# main.net
KiCad netlist of a schematic drawn in Altium Designer
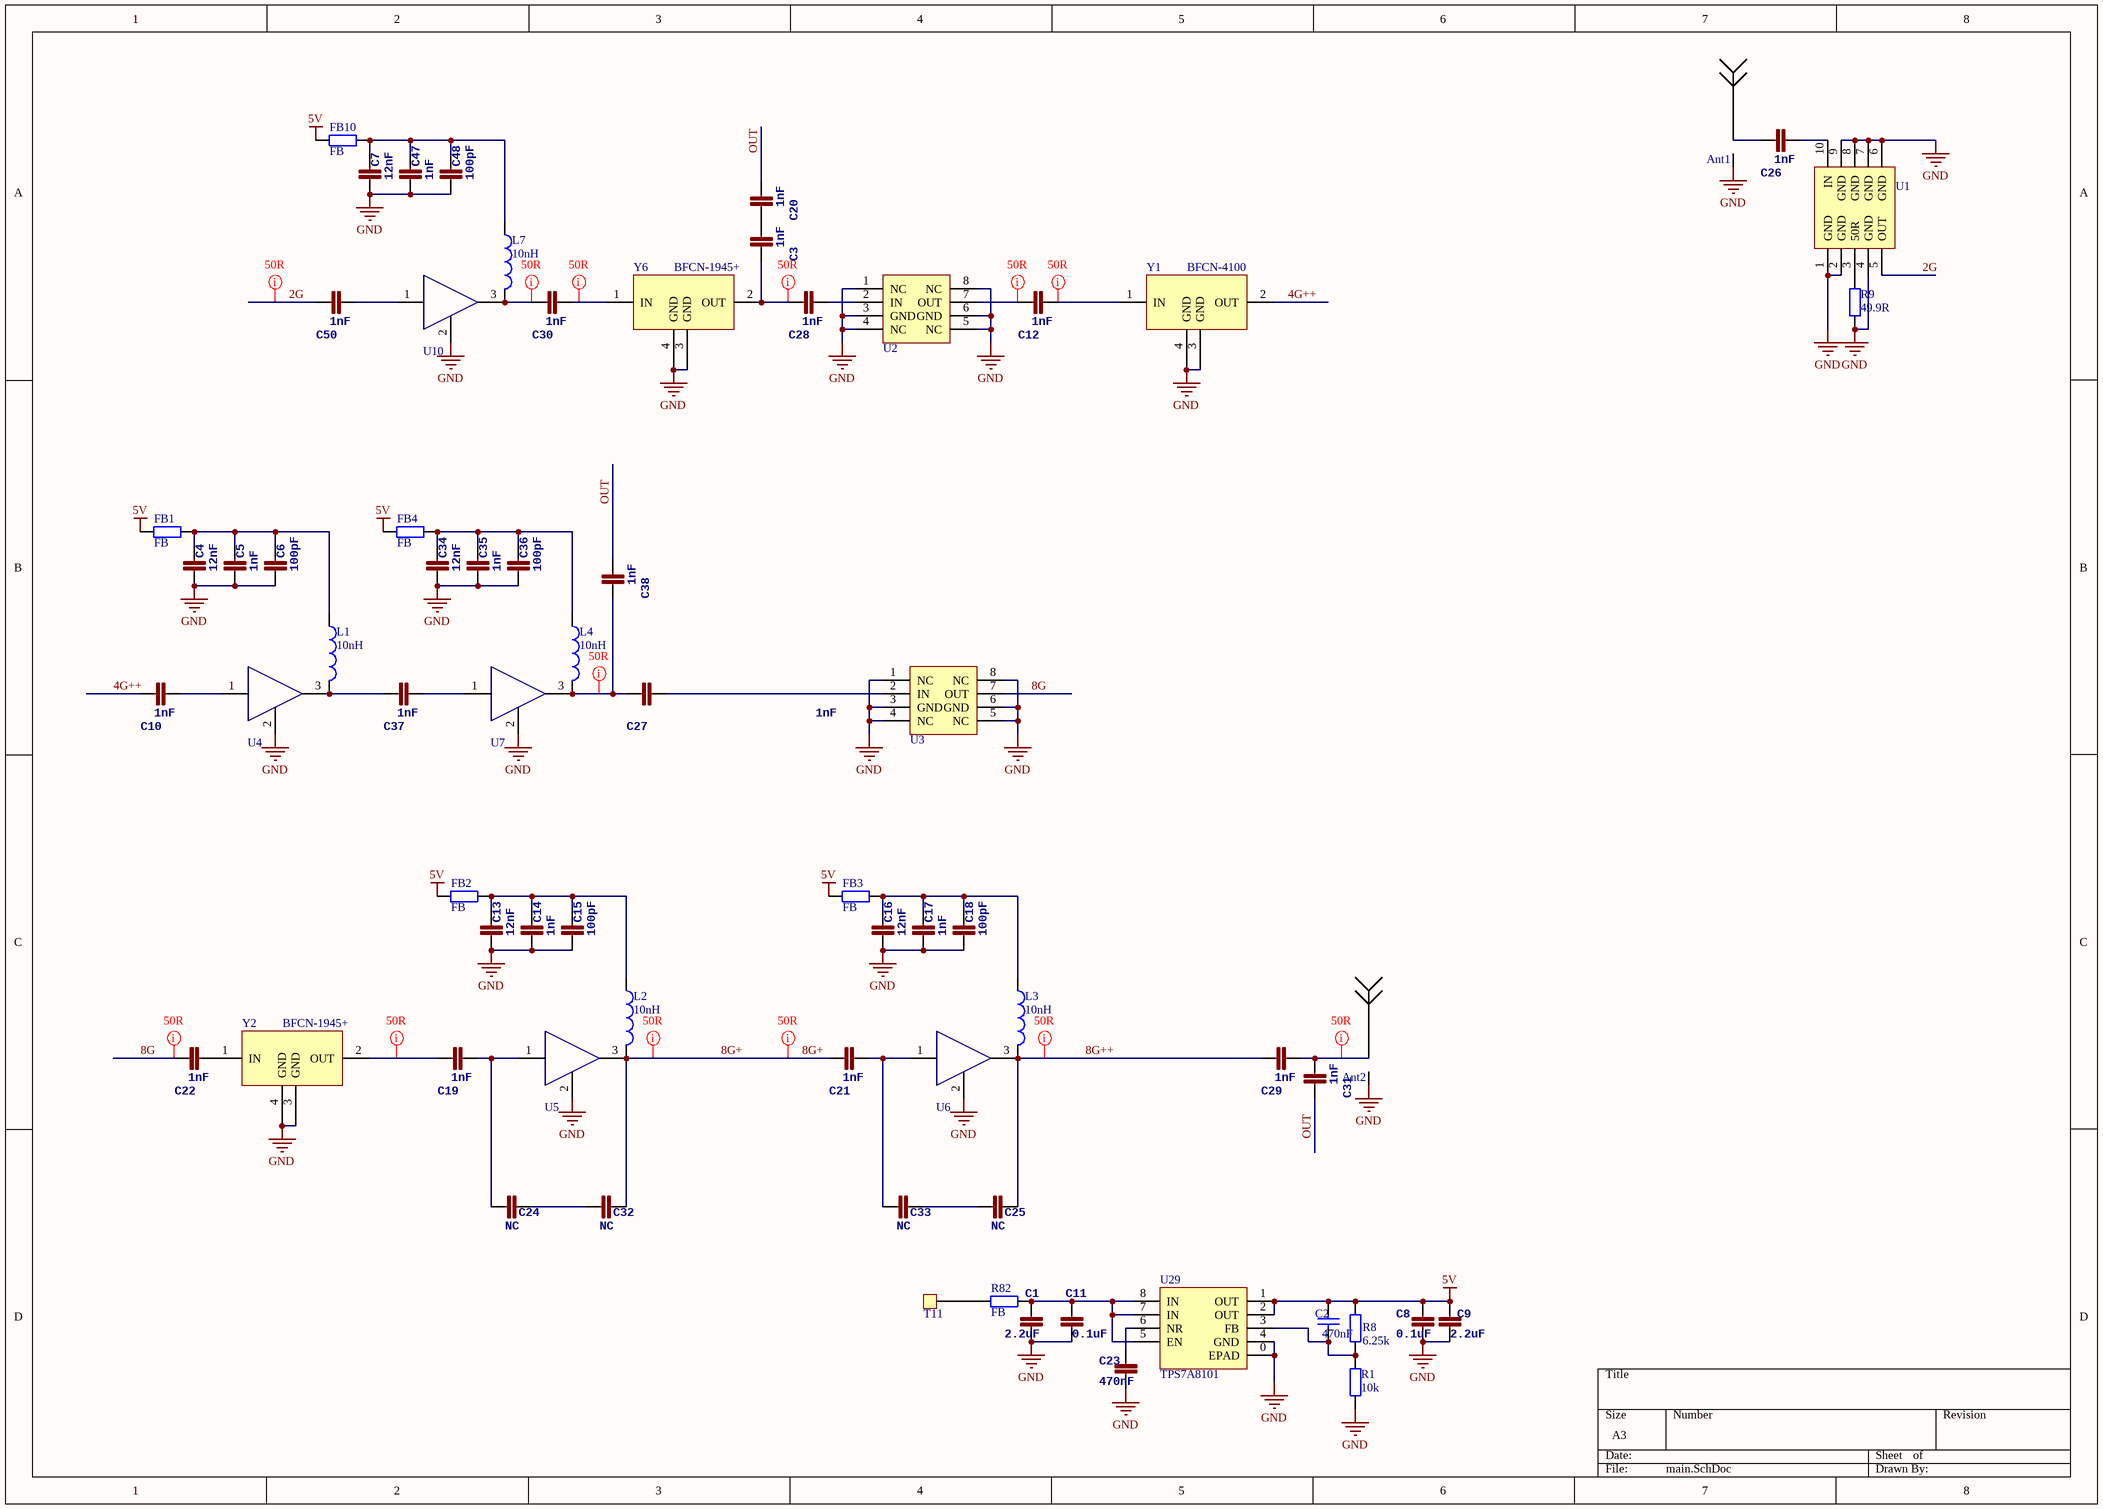
[diagram p0: main.SchDoc]

(export (version "E")
  (design (tool "Eeschema 10.0.6"))
  (components
    (comp (ref "Ant1") (value "Antenna") (footprint "SMA-2") (libsource (lib "F4SDR") (part "Antenna")))
    (comp (ref "Ant2") (value "Antenna") (footprint "SMA-2") (libsource (lib "F4SDR") (part "Antenna")))
    (comp (ref "C1")
      (value "2.2uF")
      (footprint "0603")
      (description "<b>Capacitor</b>\nStandard 0603 ceramic capacitor, and 0.1\" leaded capacitor.")
      (fields (field (name "PARTNO") "CC0402ZRY5V7BB104"))
      (libsource (lib "") (part "CAP0402-CAP_1"))
    )
    (comp (ref "C2")
      (value "470nF")
      (footprint "0402")
      (description "Capacitor")
      (fields (field (name "PUBLISHER") "Altium Limited"))
      (libsource (lib "RTC6705") (part "Cap"))
    )
    (comp (ref "C3")
      (value "1nF")
      (footprint "0603L")
      (description "<b>Capacitor</b>\nStandard 0603 ceramic capacitor, and 0.1\" leaded capacitor.")
      (fields (field (name "PARTNO") "CC0402ZRY5V7BB104"))
      (libsource (lib "") (part "CAP0402-CAP_1"))
    )
    (comp (ref "C4")
      (value "12nF")
      (footprint "0805")
      (description "<b>Capacitor</b>\nStandard 0603 ceramic capacitor, and 0.1\" leaded capacitor.")
      (fields (field (name "PARTNO") "CC0402ZRY5V7BB104"))
      (libsource (lib "") (part "CAP0402-CAP_1"))
    )
    (comp (ref "C5")
      (value "1nF")
      (footprint "0402")
      (description "<b>Capacitor</b>\nStandard 0603 ceramic capacitor, and 0.1\" leaded capacitor.")
      (fields (field (name "PARTNO") "CC0402ZRY5V7BB104"))
      (libsource (lib "") (part "CAP0402-CAP_1"))
    )
    (comp (ref "C6")
      (value "100pF")
      (footprint "0402")
      (description "<b>Capacitor</b>\nStandard 0603 ceramic capacitor, and 0.1\" leaded capacitor.")
      (fields (field (name "PARTNO") "CC0402ZRY5V7BB104"))
      (libsource (lib "") (part "CAP0402-CAP_1"))
    )
    (comp (ref "C7")
      (value "12nF")
      (footprint "0805")
      (description "<b>Capacitor</b>\nStandard 0603 ceramic capacitor, and 0.1\" leaded capacitor.")
      (fields (field (name "PARTNO") "CC0402ZRY5V7BB104"))
      (libsource (lib "") (part "CAP0402-CAP_1"))
    )
    (comp (ref "C8")
      (value "0.1uF")
      (footprint "0603")
      (description "<b>Capacitor</b>\nStandard 0603 ceramic capacitor, and 0.1\" leaded capacitor.")
      (fields (field (name "PARTNO") "CC0402ZRY5V7BB104"))
      (libsource (lib "*") (part "CAP0402-CAP"))
    )
    (comp (ref "C9")
      (value "2.2uF")
      (footprint "0603")
      (description "<b>Capacitor</b>\nStandard 0603 ceramic capacitor, and 0.1\" leaded capacitor.")
      (fields (field (name "PARTNO") "CC0402ZRY5V7BB104"))
      (libsource (lib "") (part "CAP0402-CAP_1"))
    )
    (comp (ref "C10")
      (value "1nF")
      (footprint "0603L")
      (description "<b>Capacitor</b>\nStandard 0603 ceramic capacitor, and 0.1\" leaded capacitor.")
      (fields (field (name "PARTNO") "CC0402ZRY5V7BB104"))
      (libsource (lib "pixhawk2") (part "CAP0402-CAP"))
    )
    (comp (ref "C11")
      (value "0.1uF")
      (footprint "0402")
      (description "<b>Capacitor</b>\nStandard 0603 ceramic capacitor, and 0.1\" leaded capacitor.")
      (fields (field (name "PARTNO") "CC0402ZRY5V7BB104"))
      (libsource (lib "*") (part "CAP0402-CAP"))
    )
    (comp (ref "C12")
      (value "1nF")
      (footprint "0603L")
      (description "<b>Capacitor</b>\nStandard 0603 ceramic capacitor, and 0.1\" leaded capacitor.")
      (fields (field (name "PARTNO") "CC0402ZRY5V7BB104"))
      (libsource (lib "pixhawk2") (part "CAP0402-CAP"))
    )
    (comp (ref "C13")
      (value "12nF")
      (footprint "0805")
      (description "<b>Capacitor</b>\nStandard 0603 ceramic capacitor, and 0.1\" leaded capacitor.")
      (fields (field (name "PARTNO") "CC0402ZRY5V7BB104"))
      (libsource (lib "") (part "CAP0402-CAP_1"))
    )
    (comp (ref "C14")
      (value "1nF")
      (footprint "0402")
      (description "<b>Capacitor</b>\nStandard 0603 ceramic capacitor, and 0.1\" leaded capacitor.")
      (fields (field (name "PARTNO") "CC0402ZRY5V7BB104"))
      (libsource (lib "") (part "CAP0402-CAP_1"))
    )
    (comp (ref "C15")
      (value "100pF")
      (footprint "0402")
      (description "<b>Capacitor</b>\nStandard 0603 ceramic capacitor, and 0.1\" leaded capacitor.")
      (fields (field (name "PARTNO") "CC0402ZRY5V7BB104"))
      (libsource (lib "") (part "CAP0402-CAP_1"))
    )
    (comp (ref "C16")
      (value "12nF")
      (footprint "0805")
      (description "<b>Capacitor</b>\nStandard 0603 ceramic capacitor, and 0.1\" leaded capacitor.")
      (fields (field (name "PARTNO") "CC0402ZRY5V7BB104"))
      (libsource (lib "") (part "CAP0402-CAP_1"))
    )
    (comp (ref "C17")
      (value "1nF")
      (footprint "0402")
      (description "<b>Capacitor</b>\nStandard 0603 ceramic capacitor, and 0.1\" leaded capacitor.")
      (fields (field (name "PARTNO") "CC0402ZRY5V7BB104"))
      (libsource (lib "") (part "CAP0402-CAP_1"))
    )
    (comp (ref "C18")
      (value "100pF")
      (footprint "0402")
      (description "<b>Capacitor</b>\nStandard 0603 ceramic capacitor, and 0.1\" leaded capacitor.")
      (fields (field (name "PARTNO") "CC0402ZRY5V7BB104"))
      (libsource (lib "") (part "CAP0402-CAP_1"))
    )
    (comp (ref "C19")
      (value "1nF")
      (footprint "0603L")
      (description "<b>Capacitor</b>\nStandard 0603 ceramic capacitor, and 0.1\" leaded capacitor.")
      (fields (field (name "PARTNO") "CC0402ZRY5V7BB104"))
      (libsource (lib "pixhawk2") (part "CAP0402-CAP"))
    )
    (comp (ref "C20")
      (value "1nF")
      (footprint "0603L")
      (description "<b>Capacitor</b>\nStandard 0603 ceramic capacitor, and 0.1\" leaded capacitor.")
      (fields (field (name "PARTNO") "CC0402ZRY5V7BB104"))
      (libsource (lib "") (part "CAP0402-CAP_1"))
    )
    (comp (ref "C21")
      (value "1nF")
      (footprint "0603L")
      (description "<b>Capacitor</b>\nStandard 0603 ceramic capacitor, and 0.1\" leaded capacitor.")
      (fields (field (name "PARTNO") "CC0402ZRY5V7BB104"))
      (libsource (lib "pixhawk2") (part "CAP0402-CAP"))
    )
    (comp (ref "C22")
      (value "1nF")
      (footprint "0603L")
      (description "<b>Capacitor</b>\nStandard 0603 ceramic capacitor, and 0.1\" leaded capacitor.")
      (fields (field (name "PARTNO") "CC0402ZRY5V7BB104"))
      (libsource (lib "pixhawk2") (part "CAP0402-CAP"))
    )
    (comp (ref "C23")
      (value "470nF")
      (footprint "0402")
      (description "<b>Capacitor</b>\nStandard 0603 ceramic capacitor, and 0.1\" leaded capacitor.")
      (fields (field (name "PARTNO") "CC0402ZRY5V7BB104"))
      (libsource (lib "*") (part "CAP0402-CAP"))
    )
    (comp (ref "C24")
      (value "NC")
      (footprint "0402")
      (description "<b>Capacitor</b>\nStandard 0603 ceramic capacitor, and 0.1\" leaded capacitor.")
      (fields (field (name "PARTNO") "CC0402ZRY5V7BB104"))
      (libsource (lib "pixhawk2") (part "CAP0402-CAP"))
    )
    (comp (ref "C25")
      (value "NC")
      (footprint "0402")
      (description "<b>Capacitor</b>\nStandard 0603 ceramic capacitor, and 0.1\" leaded capacitor.")
      (fields (field (name "PARTNO") "CC0402ZRY5V7BB104"))
      (libsource (lib "pixhawk2") (part "CAP0402-CAP"))
    )
    (comp (ref "C26")
      (value "1nF")
      (footprint "0603L")
      (description "<b>Capacitor</b>\nStandard 0603 ceramic capacitor, and 0.1\" leaded capacitor.")
      (fields (field (name "PARTNO") "CC0402ZRY5V7BB104"))
      (libsource (lib "pixhawk2") (part "CAP0402-CAP"))
    )
    (comp (ref "C27")
      (value "1nF")
      (footprint "0603L")
      (description "<b>Capacitor</b>\nStandard 0603 ceramic capacitor, and 0.1\" leaded capacitor.")
      (fields (field (name "PARTNO") "CC0402ZRY5V7BB104"))
      (libsource (lib "pixhawk2") (part "CAP0402-CAP"))
    )
    (comp (ref "C28")
      (value "1nF")
      (footprint "0603L")
      (description "<b>Capacitor</b>\nStandard 0603 ceramic capacitor, and 0.1\" leaded capacitor.")
      (fields (field (name "PARTNO") "CC0402ZRY5V7BB104"))
      (libsource (lib "pixhawk2") (part "CAP0402-CAP"))
    )
    (comp (ref "C29")
      (value "1nF")
      (footprint "0603L")
      (description "<b>Capacitor</b>\nStandard 0603 ceramic capacitor, and 0.1\" leaded capacitor.")
      (fields (field (name "PARTNO") "CC0402ZRY5V7BB104"))
      (libsource (lib "pixhawk2") (part "CAP0402-CAP"))
    )
    (comp (ref "C30")
      (value "1nF")
      (footprint "0603L")
      (description "<b>Capacitor</b>\nStandard 0603 ceramic capacitor, and 0.1\" leaded capacitor.")
      (fields (field (name "PARTNO") "CC0402ZRY5V7BB104"))
      (libsource (lib "pixhawk2") (part "CAP0402-CAP"))
    )
    (comp (ref "C31")
      (value "1nF")
      (footprint "0603L")
      (description "<b>Capacitor</b>\nStandard 0603 ceramic capacitor, and 0.1\" leaded capacitor.")
      (fields (field (name "PARTNO") "CC0402ZRY5V7BB104"))
      (libsource (lib "") (part "CAP0402-CAP_1"))
    )
    (comp (ref "C32")
      (value "NC")
      (footprint "0402")
      (description "<b>Capacitor</b>\nStandard 0603 ceramic capacitor, and 0.1\" leaded capacitor.")
      (fields (field (name "PARTNO") "CC0402ZRY5V7BB104"))
      (libsource (lib "pixhawk2") (part "CAP0402-CAP"))
    )
    (comp (ref "C33")
      (value "NC")
      (footprint "0402")
      (description "<b>Capacitor</b>\nStandard 0603 ceramic capacitor, and 0.1\" leaded capacitor.")
      (fields (field (name "PARTNO") "CC0402ZRY5V7BB104"))
      (libsource (lib "pixhawk2") (part "CAP0402-CAP"))
    )
    (comp (ref "C34")
      (value "12nF")
      (footprint "0805")
      (description "<b>Capacitor</b>\nStandard 0603 ceramic capacitor, and 0.1\" leaded capacitor.")
      (fields (field (name "PARTNO") "CC0402ZRY5V7BB104"))
      (libsource (lib "") (part "CAP0402-CAP_1"))
    )
    (comp (ref "C35")
      (value "1nF")
      (footprint "0402")
      (description "<b>Capacitor</b>\nStandard 0603 ceramic capacitor, and 0.1\" leaded capacitor.")
      (fields (field (name "PARTNO") "CC0402ZRY5V7BB104"))
      (libsource (lib "") (part "CAP0402-CAP_1"))
    )
    (comp (ref "C36")
      (value "100pF")
      (footprint "0402")
      (description "<b>Capacitor</b>\nStandard 0603 ceramic capacitor, and 0.1\" leaded capacitor.")
      (fields (field (name "PARTNO") "CC0402ZRY5V7BB104"))
      (libsource (lib "") (part "CAP0402-CAP_1"))
    )
    (comp (ref "C37")
      (value "1nF")
      (footprint "0603L")
      (description "<b>Capacitor</b>\nStandard 0603 ceramic capacitor, and 0.1\" leaded capacitor.")
      (fields (field (name "PARTNO") "CC0402ZRY5V7BB104"))
      (libsource (lib "pixhawk2") (part "CAP0402-CAP"))
    )
    (comp (ref "C38")
      (value "1nF")
      (footprint "0603L")
      (description "<b>Capacitor</b>\nStandard 0603 ceramic capacitor, and 0.1\" leaded capacitor.")
      (fields (field (name "PARTNO") "CC0402ZRY5V7BB104"))
      (libsource (lib "") (part "CAP0402-CAP_1"))
    )
    (comp (ref "C47")
      (value "1nF")
      (footprint "0402")
      (description "<b>Capacitor</b>\nStandard 0603 ceramic capacitor, and 0.1\" leaded capacitor.")
      (fields (field (name "PARTNO") "CC0402ZRY5V7BB104"))
      (libsource (lib "") (part "CAP0402-CAP_1"))
    )
    (comp (ref "C48")
      (value "100pF")
      (footprint "0402")
      (description "<b>Capacitor</b>\nStandard 0603 ceramic capacitor, and 0.1\" leaded capacitor.")
      (fields (field (name "PARTNO") "CC0402ZRY5V7BB104"))
      (libsource (lib "") (part "CAP0402-CAP_1"))
    )
    (comp (ref "C50")
      (value "1nF")
      (footprint "0603L")
      (description "<b>Capacitor</b>\nStandard 0603 ceramic capacitor, and 0.1\" leaded capacitor.")
      (fields (field (name "PARTNO") "CC0402ZRY5V7BB104"))
      (libsource (lib "pixhawk2") (part "CAP0402-CAP"))
    )
    (comp (ref "FB1")
      (value "FB")
      (footprint "0603")
      (description "Resistor")
      (fields (field (name "PUBLISHER") "Altium Limited"))
      (libsource (lib "") (part "Res2_1"))
    )
    (comp (ref "FB2")
      (value "FB")
      (footprint "0603")
      (description "Resistor")
      (fields (field (name "PUBLISHER") "Altium Limited"))
      (libsource (lib "") (part "Res2_1"))
    )
    (comp (ref "FB3")
      (value "FB")
      (footprint "0603")
      (description "Resistor")
      (fields (field (name "PUBLISHER") "Altium Limited"))
      (libsource (lib "") (part "Res2_1"))
    )
    (comp (ref "FB4")
      (value "FB")
      (footprint "0603")
      (description "Resistor")
      (fields (field (name "PUBLISHER") "Altium Limited"))
      (libsource (lib "") (part "Res2_1"))
    )
    (comp (ref "FB10")
      (value "FB")
      (footprint "0603")
      (description "Resistor")
      (fields (field (name "PUBLISHER") "Altium Limited"))
      (libsource (lib "") (part "Res2_1"))
    )
    (comp (ref "L1")
      (value "10nH")
      (footprint "0402")
      (description "Inductor")
      (fields (field (name "PUBLISHER") "Altium Limited"))
      (libsource (lib "Miscellaneous Devices") (part "Inductor"))
    )
    (comp (ref "L2")
      (value "10nH")
      (footprint "0402")
      (description "Inductor")
      (fields (field (name "PUBLISHER") "Altium Limited"))
      (libsource (lib "Miscellaneous Devices") (part "Inductor"))
    )
    (comp (ref "L3")
      (value "10nH")
      (footprint "0402")
      (description "Inductor")
      (fields (field (name "PUBLISHER") "Altium Limited"))
      (libsource (lib "Miscellaneous Devices") (part "Inductor"))
    )
    (comp (ref "L4")
      (value "10nH")
      (footprint "0402")
      (description "Inductor")
      (fields (field (name "PUBLISHER") "Altium Limited"))
      (libsource (lib "Miscellaneous Devices") (part "Inductor"))
    )
    (comp (ref "L7")
      (value "10nH")
      (footprint "0402")
      (description "Inductor")
      (fields (field (name "PUBLISHER") "Altium Limited"))
      (libsource (lib "Miscellaneous Devices") (part "Inductor"))
    )
    (comp (ref "R1")
      (value "10k")
      (footprint "0402")
      (description "Resistor")
      (fields (field (name "PUBLISHER") "Altium Limited"))
      (libsource (lib "Miscellaneous Devices") (part "Res2"))
    )
    (comp (ref "R8")
      (value "6.25k")
      (footprint "0402")
      (description "Resistor")
      (fields (field (name "PUBLISHER") "Altium Limited"))
      (libsource (lib "Miscellaneous Devices") (part "Res2"))
    )
    (comp (ref "R9")
      (value "49.9R")
      (footprint "0402")
      (description "Resistor")
      (fields (field (name "PUBLISHER") "Altium Limited"))
      (libsource (lib "") (part "Res2_2"))
    )
    (comp (ref "R82")
      (value "FB")
      (footprint "0603L")
      (description "Resistor")
      (fields (field (name "PUBLISHER") "Altium Limited"))
      (libsource (lib "") (part "Res2_3"))
    )
    (comp (ref "T11") (value "TestPad") (footprint "TestPad - 1mm") (libsource (lib "sch") (part "TestPad")))
    (comp (ref "U1") (value "KC2-11+") (footprint "DZ885") (libsource (lib "F4SDR") (part "KC2-11+")))
    (comp (ref "U2") (value "HMC189") (footprint "MSOP8/VSSOP8") (libsource (lib "F4SDR") (part "HMC189")))
    (comp (ref "U3") (value "HMC189") (footprint "MSOP8/VSSOP8") (libsource (lib "F4SDR") (part "HMC189")))
    (comp (ref "U4") (value "AMP-SOT89") (footprint "SOT-89") (libsource (lib "F4SDR") (part "AMP-SOT89")))
    (comp (ref "U5") (value "AMP-SOT89") (footprint "SOT-89") (libsource (lib "F4SDR") (part "AMP-SOT89")))
    (comp (ref "U6") (value "AMP-SOT89") (footprint "SOT-89") (libsource (lib "F4SDR") (part "AMP-SOT89")))
    (comp (ref "U7") (value "AMP-SOT89") (footprint "SOT-89") (libsource (lib "F4SDR") (part "AMP-SOT89")))
    (comp (ref "U10") (value "AMP-SOT89") (footprint "SOT-89") (libsource (lib "F4SDR") (part "AMP-SOT89")))
    (comp (ref "U29")
      (value "TPS7A8101")
      (footprint "TPS7A8101")
      (libsource (lib "F4SDR") (part "TPS7A8101"))
    )
    (comp (ref "Y1")
      (value "BFCN-4100")
      (footprint "1748LP18A075")
      (libsource (lib "F4SDR") (part "1748LP18A075"))
    )
    (comp (ref "Y2")
      (value "BFCN-1945+")
      (footprint "1748LP18A075")
      (libsource (lib "F4SDR") (part "1748LP18A075"))
    )
    (comp (ref "Y6")
      (value "BFCN-1945+")
      (footprint "1748LP18A075")
      (libsource (lib "F4SDR") (part "1748LP18A075"))
    )
  )
  (nets
    (net (code "1") (name "/2G") (class "Default")
      (node (ref "C50") (pin "1") (pinfunction "1_1") (pintype "passive"))
      (node (ref "U1") (pin "5") (pinfunction "OUT_5") (pintype "passive"))
    )
    (net (code "2") (name "/4G++") (class "Default")
      (node (ref "C10") (pin "1") (pinfunction "1_1") (pintype "passive"))
      (node (ref "Y1") (pin "2") (pinfunction "OUT_2") (pintype "passive"))
    )
    (net (code "3") (name "/8G") (class "Default")
      (node (ref "C22") (pin "1") (pinfunction "1_1") (pintype "passive"))
      (node (ref "U3") (pin "7") (pinfunction "OUT_7") (pintype "passive"))
    )
    (net (code "4") (name "/8G+") (class "Default")
      (node (ref "C21") (pin "1") (pinfunction "1_1") (pintype "passive"))
      (node (ref "C32") (pin "2") (pinfunction "2_2") (pintype "passive"))
      (node (ref "L2") (pin "2") (pinfunction "2_2") (pintype "passive"))
      (node (ref "U5") (pin "3") (pinfunction "3_3") (pintype "passive"))
    )
    (net (code "5") (name "/8G++") (class "Default")
      (node (ref "C25") (pin "2") (pinfunction "2_2") (pintype "passive"))
      (node (ref "C29") (pin "1") (pinfunction "1_1") (pintype "passive"))
      (node (ref "L3") (pin "2") (pinfunction "2_2") (pintype "passive"))
      (node (ref "U6") (pin "3") (pinfunction "3_3") (pintype "passive"))
    )
    (net (code "6") (name "/OUT") (class "Default")
      (node (ref "C20") (pin "2") (pinfunction "2_2") (pintype "passive"))
      (node (ref "C31") (pin "1") (pinfunction "1_1") (pintype "passive"))
      (node (ref "C38") (pin "2") (pinfunction "2_2") (pintype "passive"))
    )
    (net (code "7") (name "5V") (class "Default")
      (node (ref "C2") (pin "1") (pinfunction "1_1") (pintype "passive"))
      (node (ref "C8") (pin "2") (pinfunction "2_2") (pintype "passive"))
      (node (ref "C9") (pin "2") (pinfunction "2_2") (pintype "passive"))
      (node (ref "FB1") (pin "1") (pinfunction "1_1") (pintype "passive"))
      (node (ref "FB10") (pin "1") (pinfunction "1_1") (pintype "passive"))
      (node (ref "FB2") (pin "1") (pinfunction "1_1") (pintype "passive"))
      (node (ref "FB3") (pin "1") (pinfunction "1_1") (pintype "passive"))
      (node (ref "FB4") (pin "1") (pinfunction "1_1") (pintype "passive"))
      (node (ref "R8") (pin "1") (pinfunction "1_1") (pintype "passive"))
      (node (ref "U29") (pin "1") (pinfunction "OUT_1") (pintype "passive"))
      (node (ref "U29") (pin "2") (pinfunction "OUT_2") (pintype "passive"))
    )
    (net (code "8") (name "GND") (class "Default")
      (node (ref "Ant1") (pin "GND") (pinfunction "G_GND") (pintype "passive"))
      (node (ref "Ant2") (pin "GND") (pinfunction "G_GND") (pintype "passive"))
      (node (ref "C1") (pin "1") (pinfunction "1_1") (pintype "passive"))
      (node (ref "C11") (pin "1") (pinfunction "1_1") (pintype "passive"))
      (node (ref "C13") (pin "1") (pinfunction "1_1") (pintype "passive"))
      (node (ref "C14") (pin "1") (pinfunction "1_1") (pintype "passive"))
      (node (ref "C15") (pin "1") (pinfunction "1_1") (pintype "passive"))
      (node (ref "C16") (pin "1") (pinfunction "1_1") (pintype "passive"))
      (node (ref "C17") (pin "1") (pinfunction "1_1") (pintype "passive"))
      (node (ref "C18") (pin "1") (pinfunction "1_1") (pintype "passive"))
      (node (ref "C23") (pin "1") (pinfunction "1_1") (pintype "passive"))
      (node (ref "C34") (pin "1") (pinfunction "1_1") (pintype "passive"))
      (node (ref "C35") (pin "1") (pinfunction "1_1") (pintype "passive"))
      (node (ref "C36") (pin "1") (pinfunction "1_1") (pintype "passive"))
      (node (ref "C4") (pin "1") (pinfunction "1_1") (pintype "passive"))
      (node (ref "C47") (pin "1") (pinfunction "1_1") (pintype "passive"))
      (node (ref "C48") (pin "1") (pinfunction "1_1") (pintype "passive"))
      (node (ref "C5") (pin "1") (pinfunction "1_1") (pintype "passive"))
      (node (ref "C6") (pin "1") (pinfunction "1_1") (pintype "passive"))
      (node (ref "C7") (pin "1") (pinfunction "1_1") (pintype "passive"))
      (node (ref "C8") (pin "1") (pinfunction "1_1") (pintype "passive"))
      (node (ref "C9") (pin "1") (pinfunction "1_1") (pintype "passive"))
      (node (ref "R1") (pin "2") (pinfunction "2_2") (pintype "passive"))
      (node (ref "R9") (pin "1") (pinfunction "1_1") (pintype "passive"))
      (node (ref "U1") (pin "1") (pinfunction "GND_1") (pintype "passive"))
      (node (ref "U1") (pin "2") (pinfunction "GND_2") (pintype "passive"))
      (node (ref "U1") (pin "4") (pinfunction "GND_4") (pintype "passive"))
      (node (ref "U1") (pin "6") (pinfunction "GND_6") (pintype "passive"))
      (node (ref "U1") (pin "7") (pinfunction "GND_7") (pintype "passive"))
      (node (ref "U1") (pin "8") (pinfunction "GND_8") (pintype "passive"))
      (node (ref "U1") (pin "9") (pinfunction "GND_9") (pintype "passive"))
      (node (ref "U10") (pin "2") (pinfunction "2_2") (pintype "passive"))
      (node (ref "U2") (pin "1") (pinfunction "NC_1") (pintype "passive"))
      (node (ref "U2") (pin "3") (pinfunction "GND_3") (pintype "passive"))
      (node (ref "U2") (pin "4") (pinfunction "NC_4") (pintype "passive"))
      (node (ref "U2") (pin "5") (pinfunction "NC_5") (pintype "passive"))
      (node (ref "U2") (pin "6") (pinfunction "GND_6") (pintype "passive"))
      (node (ref "U2") (pin "8") (pinfunction "NC_8") (pintype "passive"))
      (node (ref "U29") (pin "0") (pinfunction "EPAD_0") (pintype "passive"))
      (node (ref "U29") (pin "4") (pinfunction "GND_4") (pintype "passive"))
      (node (ref "U3") (pin "1") (pinfunction "NC_1") (pintype "passive"))
      (node (ref "U3") (pin "3") (pinfunction "GND_3") (pintype "passive"))
      (node (ref "U3") (pin "4") (pinfunction "NC_4") (pintype "passive"))
      (node (ref "U3") (pin "5") (pinfunction "NC_5") (pintype "passive"))
      (node (ref "U3") (pin "6") (pinfunction "GND_6") (pintype "passive"))
      (node (ref "U3") (pin "8") (pinfunction "NC_8") (pintype "passive"))
      (node (ref "U4") (pin "2") (pinfunction "2_2") (pintype "passive"))
      (node (ref "U5") (pin "2") (pinfunction "2_2") (pintype "passive"))
      (node (ref "U6") (pin "2") (pinfunction "2_2") (pintype "passive"))
      (node (ref "U7") (pin "2") (pinfunction "2_2") (pintype "passive"))
      (node (ref "Y1") (pin "3") (pinfunction "GND_3") (pintype "passive"))
      (node (ref "Y1") (pin "4") (pinfunction "GND_4") (pintype "passive"))
      (node (ref "Y2") (pin "3") (pinfunction "GND_3") (pintype "passive"))
      (node (ref "Y2") (pin "4") (pinfunction "GND_4") (pintype "passive"))
      (node (ref "Y6") (pin "3") (pinfunction "GND_3") (pintype "passive"))
      (node (ref "Y6") (pin "4") (pinfunction "GND_4") (pintype "passive"))
    )
    (net (code "9") (name "Net-(Ant1-Pad1)") (class "Default")
      (node (ref "Ant1") (pin "1") (pinfunction "1_1") (pintype "passive"))
      (node (ref "C26") (pin "1") (pinfunction "1_1") (pintype "passive"))
    )
    (net (code "10") (name "Net-(Ant2-Pad1)") (class "Default")
      (node (ref "Ant2") (pin "1") (pinfunction "1_1") (pintype "passive"))
      (node (ref "C29") (pin "2") (pinfunction "2_2") (pintype "passive"))
      (node (ref "C31") (pin "2") (pinfunction "2_2") (pintype "passive"))
    )
    (net (code "11") (name "Net-(C4-Pad2)") (class "Default")
      (node (ref "C4") (pin "2") (pinfunction "2_2") (pintype "passive"))
      (node (ref "C5") (pin "2") (pinfunction "2_2") (pintype "passive"))
      (node (ref "C6") (pin "2") (pinfunction "2_2") (pintype "passive"))
      (node (ref "FB1") (pin "2") (pinfunction "2_2") (pintype "passive"))
      (node (ref "L1") (pin "1") (pinfunction "1_1") (pintype "passive"))
    )
    (net (code "12") (name "Net-(C10-Pad2)") (class "Default")
      (node (ref "C10") (pin "2") (pinfunction "2_2") (pintype "passive"))
      (node (ref "U4") (pin "1") (pinfunction "1_1") (pintype "passive"))
    )
    (net (code "13") (name "Net-(C13-Pad2)") (class "Default")
      (node (ref "C13") (pin "2") (pinfunction "2_2") (pintype "passive"))
      (node (ref "C14") (pin "2") (pinfunction "2_2") (pintype "passive"))
      (node (ref "C15") (pin "2") (pinfunction "2_2") (pintype "passive"))
      (node (ref "FB2") (pin "2") (pinfunction "2_2") (pintype "passive"))
      (node (ref "L2") (pin "1") (pinfunction "1_1") (pintype "passive"))
    )
    (net (code "14") (name "Net-(C16-Pad2)") (class "Default")
      (node (ref "C16") (pin "2") (pinfunction "2_2") (pintype "passive"))
      (node (ref "C17") (pin "2") (pinfunction "2_2") (pintype "passive"))
      (node (ref "C18") (pin "2") (pinfunction "2_2") (pintype "passive"))
      (node (ref "FB3") (pin "2") (pinfunction "2_2") (pintype "passive"))
      (node (ref "L3") (pin "1") (pinfunction "1_1") (pintype "passive"))
    )
    (net (code "15") (name "Net-(C19-Pad2)") (class "Default")
      (node (ref "C19") (pin "2") (pinfunction "2_2") (pintype "passive"))
      (node (ref "C24") (pin "1") (pinfunction "1_1") (pintype "passive"))
      (node (ref "U5") (pin "1") (pinfunction "1_1") (pintype "passive"))
    )
    (net (code "16") (name "Net-(C20-Pad1)") (class "Default")
      (node (ref "C20") (pin "1") (pinfunction "1_1") (pintype "passive"))
      (node (ref "C3") (pin "2") (pinfunction "2_2") (pintype "passive"))
    )
    (net (code "17") (name "Net-(C21-Pad2)") (class "Default")
      (node (ref "C21") (pin "2") (pinfunction "2_2") (pintype "passive"))
      (node (ref "C33") (pin "1") (pinfunction "1_1") (pintype "passive"))
      (node (ref "U6") (pin "1") (pinfunction "1_1") (pintype "passive"))
    )
    (net (code "18") (name "Net-(C24-Pad2)") (class "Default")
      (node (ref "C24") (pin "2") (pinfunction "2_2") (pintype "passive"))
      (node (ref "C32") (pin "1") (pinfunction "1_1") (pintype "passive"))
    )
    (net (code "19") (name "Net-(C25-Pad1)") (class "Default")
      (node (ref "C25") (pin "1") (pinfunction "1_1") (pintype "passive"))
      (node (ref "C33") (pin "2") (pinfunction "2_2") (pintype "passive"))
    )
    (net (code "20") (name "Net-(C27-Pad1)") (class "Default")
      (node (ref "C27") (pin "1") (pinfunction "1_1") (pintype "passive"))
      (node (ref "C38") (pin "1") (pinfunction "1_1") (pintype "passive"))
      (node (ref "L4") (pin "2") (pinfunction "2_2") (pintype "passive"))
      (node (ref "U7") (pin "3") (pinfunction "3_3") (pintype "passive"))
    )
    (net (code "21") (name "Net-(C30-Pad1)") (class "Default")
      (node (ref "C30") (pin "1") (pinfunction "1_1") (pintype "passive"))
      (node (ref "L7") (pin "2") (pinfunction "2_2") (pintype "passive"))
      (node (ref "U10") (pin "3") (pinfunction "3_3") (pintype "passive"))
    )
    (net (code "22") (name "Net-(C34-Pad2)") (class "Default")
      (node (ref "C34") (pin "2") (pinfunction "2_2") (pintype "passive"))
      (node (ref "C35") (pin "2") (pinfunction "2_2") (pintype "passive"))
      (node (ref "C36") (pin "2") (pinfunction "2_2") (pintype "passive"))
      (node (ref "FB4") (pin "2") (pinfunction "2_2") (pintype "passive"))
      (node (ref "L4") (pin "1") (pinfunction "1_1") (pintype "passive"))
    )
    (net (code "23") (name "Net-(C37-Pad1)") (class "Default")
      (node (ref "C37") (pin "1") (pinfunction "1_1") (pintype "passive"))
      (node (ref "L1") (pin "2") (pinfunction "2_2") (pintype "passive"))
      (node (ref "U4") (pin "3") (pinfunction "3_3") (pintype "passive"))
    )
    (net (code "24") (name "Net-(C37-Pad2)") (class "Default")
      (node (ref "C37") (pin "2") (pinfunction "2_2") (pintype "passive"))
      (node (ref "U7") (pin "1") (pinfunction "1_1") (pintype "passive"))
    )
    (net (code "25") (name "Net-(C47-Pad2)") (class "Default")
      (node (ref "C47") (pin "2") (pinfunction "2_2") (pintype "passive"))
      (node (ref "C48") (pin "2") (pinfunction "2_2") (pintype "passive"))
      (node (ref "C7") (pin "2") (pinfunction "2_2") (pintype "passive"))
      (node (ref "FB10") (pin "2") (pinfunction "2_2") (pintype "passive"))
      (node (ref "L7") (pin "1") (pinfunction "1_1") (pintype "passive"))
    )
    (net (code "26") (name "Net-(C50-Pad2)") (class "Default")
      (node (ref "C50") (pin "2") (pinfunction "2_2") (pintype "passive"))
      (node (ref "U10") (pin "1") (pinfunction "1_1") (pintype "passive"))
    )
    (net (code "27") (name "Net-(T11-3)") (class "Default")
      (node (ref "R82") (pin "2") (pinfunction "2_2") (pintype "passive"))
      (node (ref "T11") (pin "1") (pinfunction "3_1") (pintype "passive"))
    )
    (net (code "28") (name "Net-(U1-50R)") (class "Default")
      (node (ref "R9") (pin "2") (pinfunction "2_2") (pintype "passive"))
      (node (ref "U1") (pin "3") (pinfunction "50R_3") (pintype "passive"))
    )
    (net (code "29") (name "Net-(U1-IN)") (class "Default")
      (node (ref "C26") (pin "2") (pinfunction "2_2") (pintype "passive"))
      (node (ref "U1") (pin "10") (pinfunction "IN_10") (pintype "passive"))
    )
    (net (code "30") (name "Net-(U2-IN)") (class "Default")
      (node (ref "C28") (pin "2") (pinfunction "2_2") (pintype "passive"))
      (node (ref "U2") (pin "2") (pinfunction "IN_2") (pintype "passive"))
    )
    (net (code "31") (name "Net-(U2-OUT)") (class "Default")
      (node (ref "C12") (pin "1") (pinfunction "1_1") (pintype "passive"))
      (node (ref "U2") (pin "7") (pinfunction "OUT_7") (pintype "passive"))
    )
    (net (code "32") (name "Net-(U3-IN)") (class "Default")
      (node (ref "C27") (pin "2") (pinfunction "2_2") (pintype "passive"))
      (node (ref "U3") (pin "2") (pinfunction "IN_2") (pintype "passive"))
    )
    (net (code "33") (name "Net-(U29-EN)") (class "Default")
      (node (ref "C1") (pin "2") (pinfunction "2_2") (pintype "passive"))
      (node (ref "C11") (pin "2") (pinfunction "2_2") (pintype "passive"))
      (node (ref "R82") (pin "1") (pinfunction "1_1") (pintype "passive"))
      (node (ref "U29") (pin "5") (pinfunction "EN_5") (pintype "passive"))
      (node (ref "U29") (pin "7") (pinfunction "IN_7") (pintype "passive"))
      (node (ref "U29") (pin "8") (pinfunction "IN_8") (pintype "passive"))
    )
    (net (code "34") (name "Net-(U29-FB)") (class "Default")
      (node (ref "C2") (pin "2") (pinfunction "2_2") (pintype "passive"))
      (node (ref "R1") (pin "1") (pinfunction "1_1") (pintype "passive"))
      (node (ref "R8") (pin "2") (pinfunction "2_2") (pintype "passive"))
      (node (ref "U29") (pin "3") (pinfunction "FB_3") (pintype "passive"))
    )
    (net (code "35") (name "Net-(U29-NR)") (class "Default")
      (node (ref "C23") (pin "2") (pinfunction "2_2") (pintype "passive"))
      (node (ref "U29") (pin "6") (pinfunction "NR_6") (pintype "passive"))
    )
    (net (code "36") (name "Net-(Y1-IN)") (class "Default")
      (node (ref "C12") (pin "2") (pinfunction "2_2") (pintype "passive"))
      (node (ref "Y1") (pin "1") (pinfunction "IN_1") (pintype "passive"))
    )
    (net (code "37") (name "Net-(Y2-IN)") (class "Default")
      (node (ref "C22") (pin "2") (pinfunction "2_2") (pintype "passive"))
      (node (ref "Y2") (pin "1") (pinfunction "IN_1") (pintype "passive"))
    )
    (net (code "38") (name "Net-(Y2-OUT)") (class "Default")
      (node (ref "C19") (pin "1") (pinfunction "1_1") (pintype "passive"))
      (node (ref "Y2") (pin "2") (pinfunction "OUT_2") (pintype "passive"))
    )
    (net (code "39") (name "Net-(Y6-IN)") (class "Default")
      (node (ref "C30") (pin "2") (pinfunction "2_2") (pintype "passive"))
      (node (ref "Y6") (pin "1") (pinfunction "IN_1") (pintype "passive"))
    )
    (net (code "40") (name "Net-(Y6-OUT)") (class "Default")
      (node (ref "C28") (pin "1") (pinfunction "1_1") (pintype "passive"))
      (node (ref "C3") (pin "1") (pinfunction "1_1") (pintype "passive"))
      (node (ref "Y6") (pin "2") (pinfunction "OUT_2") (pintype "passive"))
    )
  )
)
